# SHASwitch4.net
KiCad netlist of a schematic drawn in EAGLE
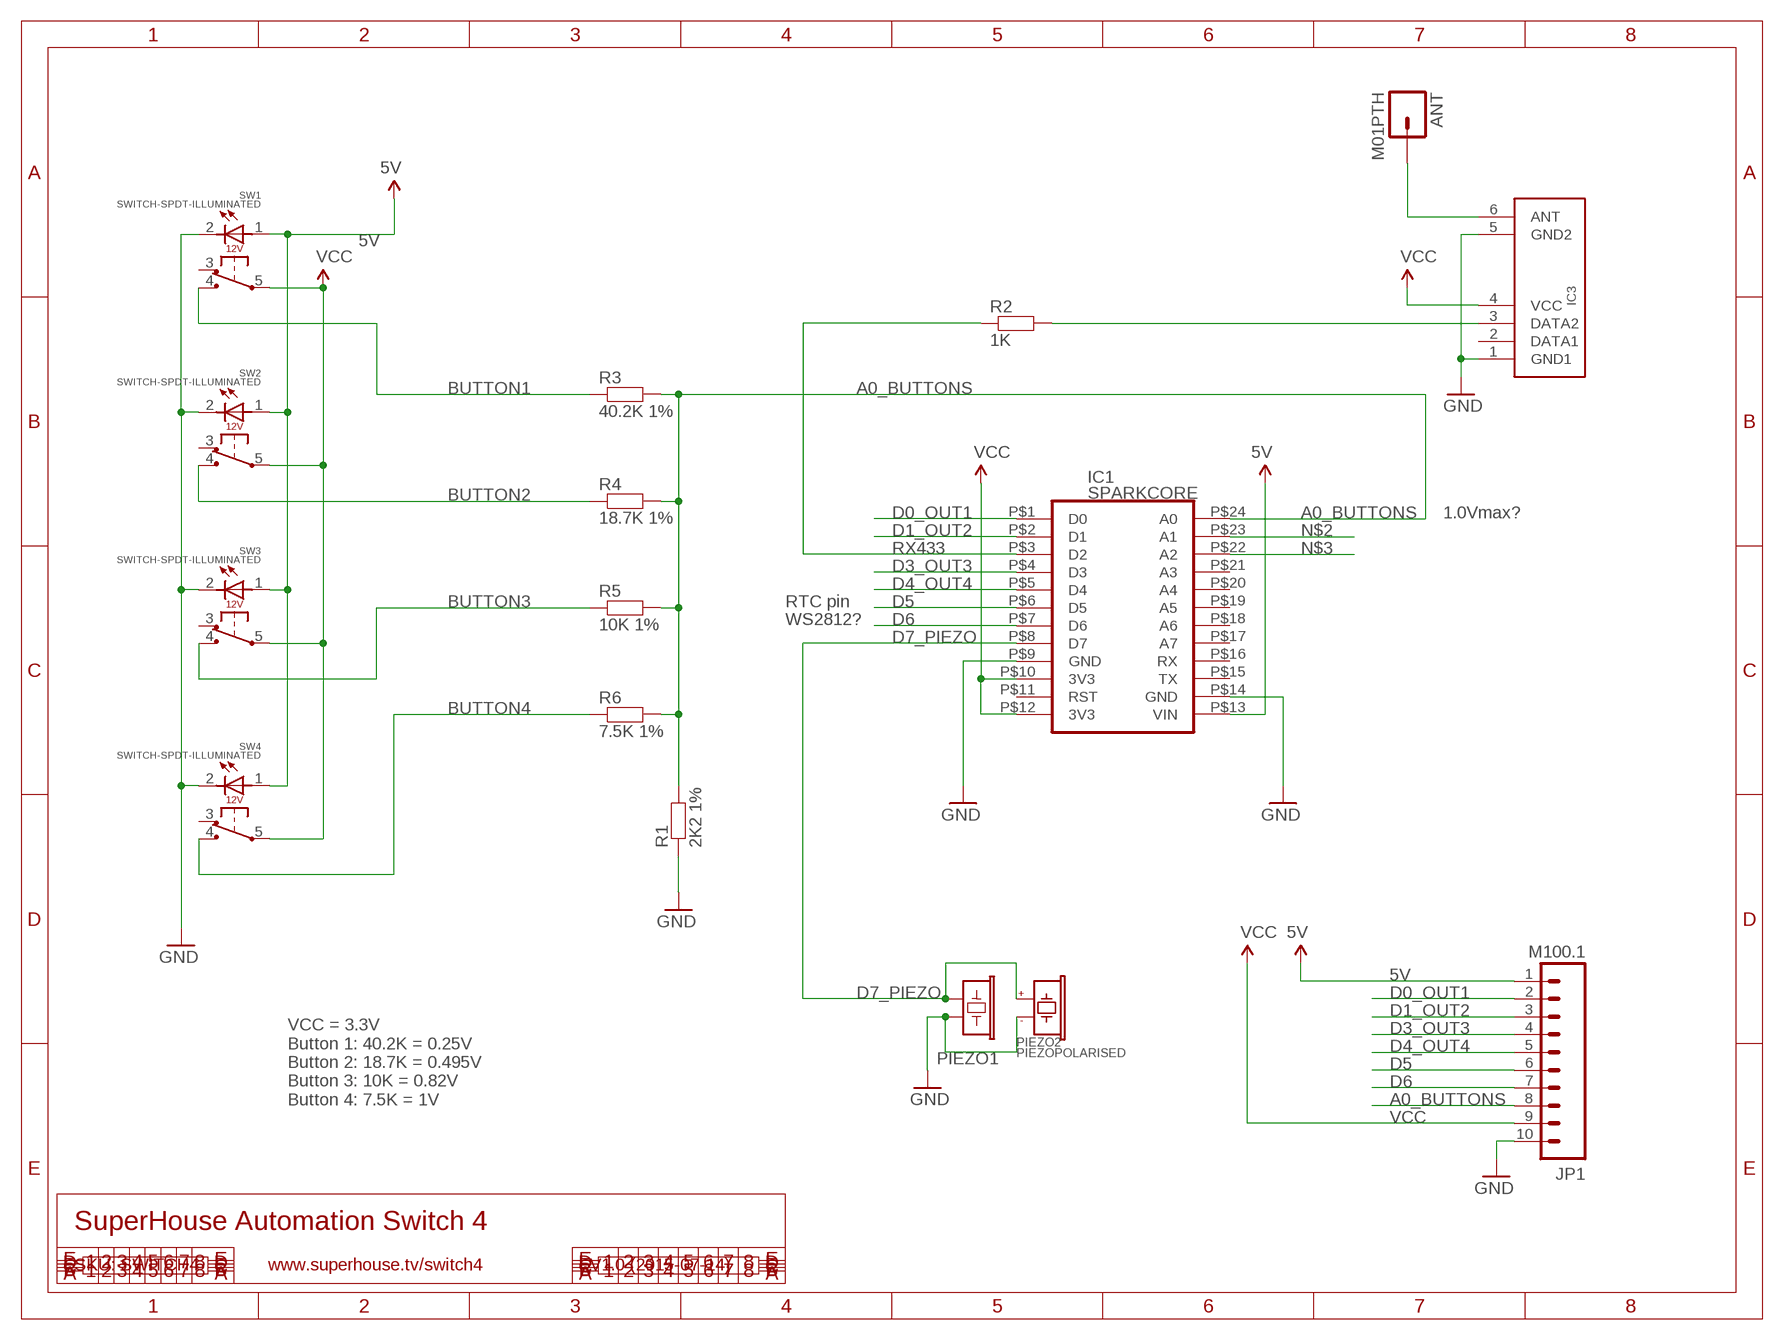
[diagram p0: schematic, sheet 1]

(export (version "E")
  (design (tool "Eeschema 10.0.6"))
  (components
    (comp (ref "ANT")
      (value "M01PTH")
      (footprint "eagle-import:1X01")
      (libsource (lib "eagle-import") (part "M01PTH"))
    )
    (comp (ref "IC1")
      (value "SPARKCORE")
      (footprint "eagle-import:SPARKCORE")
      (libsource (lib "eagle-import") (part "SPARKCORE"))
    )
    (comp (ref "IC3")
      (value "RXB1")
      (footprint "eagle-import:RX-B1-SHORT-FLAT")
      (libsource (lib "eagle-import") (part "RXB1SHORTFLAT"))
    )
    (comp (ref "JP1")
      (value "M100.1")
      (footprint "eagle-import:1X10")
      (libsource (lib "eagle-import") (part "M100.1"))
    )
    (comp (ref "PIEZO1")
      (value "BUZZERSMD12X12")
      (footprint "eagle-import:BUZZER-12X12-SMT")
      (libsource (lib "eagle-import") (part "BUZZERSMD12X12"))
    )
    (comp (ref "PIEZO2")
      (value "PIEZOPOLARISED")
      (footprint "eagle-import:PIEZO12MMWIDEPOLARISED")
      (libsource (lib "eagle-import") (part "PIEZOPOLARISED"))
    )
    (comp (ref "R1")
      (value "2K2 1%")
      (footprint "eagle-import:0603")
      (libsource (lib "eagle-import") (part "RESISTOR0603"))
    )
    (comp (ref "R2")
      (value "1K")
      (footprint "eagle-import:0603")
      (libsource (lib "eagle-import") (part "RESISTOR0603"))
    )
    (comp (ref "R3")
      (value "40.2K 1%")
      (footprint "eagle-import:0603")
      (libsource (lib "eagle-import") (part "RESISTOR0603"))
    )
    (comp (ref "R4")
      (value "18.7K 1%")
      (footprint "eagle-import:0603")
      (libsource (lib "eagle-import") (part "RESISTOR0603"))
    )
    (comp (ref "R5")
      (value "10K 1%")
      (footprint "eagle-import:0603")
      (libsource (lib "eagle-import") (part "RESISTOR0603"))
    )
    (comp (ref "R6")
      (value "7.5K 1%")
      (footprint "eagle-import:0603")
      (libsource (lib "eagle-import") (part "RESISTOR0603"))
    )
    (comp (ref "SW1")
      (value "SWITCH-SPDT-ILLUMINATED")
      (footprint "eagle-import:SWITCH-SPDT-ILLUMINATED")
      (libsource (lib "eagle-import") (part "SWITCH-SPDT-ILLUMINATED"))
    )
    (comp (ref "SW2")
      (value "SWITCH-SPDT-ILLUMINATED")
      (footprint "eagle-import:SWITCH-SPDT-ILLUMINATED")
      (libsource (lib "eagle-import") (part "SWITCH-SPDT-ILLUMINATED"))
    )
    (comp (ref "SW3")
      (value "SWITCH-SPDT-ILLUMINATED")
      (footprint "eagle-import:SWITCH-SPDT-ILLUMINATED")
      (libsource (lib "eagle-import") (part "SWITCH-SPDT-ILLUMINATED"))
    )
    (comp (ref "SW4")
      (value "SWITCH-SPDT-ILLUMINATED")
      (footprint "eagle-import:SWITCH-SPDT-ILLUMINATED")
      (libsource (lib "eagle-import") (part "SWITCH-SPDT-ILLUMINATED"))
    )
  )
  (nets
    (net (code "1") (name "/A0_BUTTONS") (class "Default")
      (node (ref "IC1") (pin "P$24") (pinfunction "A0_P$24") (pintype "bidirectional"))
      (node (ref "JP1") (pin "8") (pinfunction "8_8") (pintype "passive"))
      (node (ref "R1") (pin "2") (pinfunction "2_2") (pintype "passive"))
      (node (ref "R3") (pin "2") (pinfunction "2_2") (pintype "passive"))
      (node (ref "R4") (pin "2") (pinfunction "2_2") (pintype "passive"))
      (node (ref "R5") (pin "2") (pinfunction "2_2") (pintype "passive"))
      (node (ref "R6") (pin "2") (pinfunction "2_2") (pintype "passive"))
    )
    (net (code "2") (name "/BUTTON1") (class "Default")
      (node (ref "R3") (pin "1") (pinfunction "1_1") (pintype "passive"))
      (node (ref "SW1") (pin "4") (pinfunction "NO_4") (pintype "passive"))
    )
    (net (code "3") (name "/BUTTON2") (class "Default")
      (node (ref "R4") (pin "1") (pinfunction "1_1") (pintype "passive"))
      (node (ref "SW2") (pin "4") (pinfunction "NO_4") (pintype "passive"))
    )
    (net (code "4") (name "/BUTTON3") (class "Default")
      (node (ref "R5") (pin "1") (pinfunction "1_1") (pintype "passive"))
      (node (ref "SW3") (pin "4") (pinfunction "NO_4") (pintype "passive"))
    )
    (net (code "5") (name "/BUTTON4") (class "Default")
      (node (ref "R6") (pin "1") (pinfunction "1_1") (pintype "passive"))
      (node (ref "SW4") (pin "4") (pinfunction "NO_4") (pintype "passive"))
    )
    (net (code "6") (name "/D0_OUT1") (class "Default")
      (node (ref "IC1") (pin "P$1") (pinfunction "D0_P$1") (pintype "bidirectional"))
      (node (ref "JP1") (pin "2") (pinfunction "2_2") (pintype "passive"))
    )
    (net (code "7") (name "/D1_OUT2") (class "Default")
      (node (ref "IC1") (pin "P$2") (pinfunction "D1_P$2") (pintype "bidirectional"))
      (node (ref "JP1") (pin "3") (pinfunction "3_3") (pintype "passive"))
    )
    (net (code "8") (name "/D3_OUT3") (class "Default")
      (node (ref "IC1") (pin "P$4") (pinfunction "D3_P$4") (pintype "bidirectional"))
      (node (ref "JP1") (pin "4") (pinfunction "4_4") (pintype "passive"))
    )
    (net (code "9") (name "/D4_OUT4") (class "Default")
      (node (ref "IC1") (pin "P$5") (pinfunction "D4_P$5") (pintype "bidirectional"))
      (node (ref "JP1") (pin "5") (pinfunction "5_5") (pintype "passive"))
    )
    (net (code "10") (name "/D5") (class "Default")
      (node (ref "IC1") (pin "P$6") (pinfunction "D5_P$6") (pintype "bidirectional"))
      (node (ref "JP1") (pin "6") (pinfunction "6_6") (pintype "passive"))
    )
    (net (code "11") (name "/D6") (class "Default")
      (node (ref "IC1") (pin "P$7") (pinfunction "D6_P$7") (pintype "bidirectional"))
      (node (ref "JP1") (pin "7") (pinfunction "7_7") (pintype "passive"))
    )
    (net (code "12") (name "/D7_PIEZO") (class "Default")
      (node (ref "IC1") (pin "P$8") (pinfunction "D7_P$8") (pintype "bidirectional"))
      (node (ref "PIEZO1") (pin "1") (pinfunction "1_1") (pintype "passive"))
      (node (ref "PIEZO2") (pin "1") (pinfunction "+_1") (pintype "bidirectional"))
    )
    (net (code "13") (name "/N$2") (class "Default")
      (node (ref "IC1") (pin "P$23") (pinfunction "A1_P$23") (pintype "bidirectional"))
    )
    (net (code "14") (name "/N$3") (class "Default")
      (node (ref "IC1") (pin "P$22") (pinfunction "A2_P$22") (pintype "bidirectional"))
    )
    (net (code "15") (name "/RX433") (class "Default")
      (node (ref "IC1") (pin "P$3") (pinfunction "D2_P$3") (pintype "bidirectional"))
      (node (ref "R2") (pin "1") (pinfunction "1_1") (pintype "passive"))
    )
    (net (code "16") (name "5V") (class "Default")
      (node (ref "IC1") (pin "P$13") (pinfunction "VIN_P$13") (pintype "bidirectional"))
      (node (ref "JP1") (pin "1") (pinfunction "1_1") (pintype "passive"))
      (node (ref "SW1") (pin "1") (pinfunction "+_1") (pintype "passive"))
      (node (ref "SW2") (pin "1") (pinfunction "+_1") (pintype "passive"))
      (node (ref "SW3") (pin "1") (pinfunction "+_1") (pintype "passive"))
      (node (ref "SW4") (pin "1") (pinfunction "+_1") (pintype "passive"))
    )
    (net (code "17") (name "GND") (class "Default")
      (node (ref "IC1") (pin "P$14") (pinfunction "GND_P$14") (pintype "bidirectional"))
      (node (ref "IC1") (pin "P$9") (pinfunction "GND_P$9") (pintype "bidirectional"))
      (node (ref "IC3") (pin "1") (pinfunction "GND1_1") (pintype "bidirectional"))
      (node (ref "IC3") (pin "5") (pinfunction "GND2_5") (pintype "bidirectional"))
      (node (ref "JP1") (pin "10") (pinfunction "10_10") (pintype "passive"))
      (node (ref "PIEZO1") (pin "2") (pinfunction "2_2") (pintype "passive"))
      (node (ref "PIEZO2") (pin "2") (pinfunction "-_2") (pintype "bidirectional"))
      (node (ref "R1") (pin "1") (pinfunction "1_1") (pintype "passive"))
      (node (ref "SW1") (pin "2") (pinfunction "-_2") (pintype "passive"))
      (node (ref "SW2") (pin "2") (pinfunction "-_2") (pintype "passive"))
      (node (ref "SW3") (pin "2") (pinfunction "-_2") (pintype "passive"))
      (node (ref "SW4") (pin "2") (pinfunction "-_2") (pintype "passive"))
    )
    (net (code "18") (name "Net-(IC3-ANT)") (class "Default")
      (node (ref "ANT") (pin "1") (pinfunction "1_1") (pintype "passive"))
      (node (ref "IC3") (pin "6") (pinfunction "ANT_6") (pintype "bidirectional"))
    )
    (net (code "19") (name "Net-(IC3-DATA2)") (class "Default")
      (node (ref "IC3") (pin "3") (pinfunction "DATA2_3") (pintype "bidirectional"))
      (node (ref "R2") (pin "2") (pinfunction "2_2") (pintype "passive"))
    )
    (net (code "20") (name "VCC") (class "Default")
      (node (ref "IC1") (pin "P$10") (pinfunction "3V3_P$10") (pintype "bidirectional"))
      (node (ref "IC1") (pin "P$12") (pinfunction "3V3_P$12") (pintype "bidirectional"))
      (node (ref "IC3") (pin "4") (pinfunction "VCC_4") (pintype "bidirectional"))
      (node (ref "JP1") (pin "9") (pinfunction "9_9") (pintype "passive"))
      (node (ref "SW1") (pin "5") (pinfunction "COM_5") (pintype "passive"))
      (node (ref "SW2") (pin "5") (pinfunction "COM_5") (pintype "passive"))
      (node (ref "SW3") (pin "5") (pinfunction "COM_5") (pintype "passive"))
      (node (ref "SW4") (pin "5") (pinfunction "COM_5") (pintype "passive"))
    )
    (net (code "21") (name "unconnected-(IC1-A3-PadP$21)") (class "Default")
      (node (ref "IC1") (pin "P$21") (pinfunction "A3_P$21") (pintype "bidirectional"))
    )
    (net (code "22") (name "unconnected-(IC1-A4-PadP$20)") (class "Default")
      (node (ref "IC1") (pin "P$20") (pinfunction "A4_P$20") (pintype "bidirectional"))
    )
    (net (code "23") (name "unconnected-(IC1-A5-PadP$19)") (class "Default")
      (node (ref "IC1") (pin "P$19") (pinfunction "A5_P$19") (pintype "bidirectional"))
    )
    (net (code "24") (name "unconnected-(IC1-A6-PadP$18)") (class "Default")
      (node (ref "IC1") (pin "P$18") (pinfunction "A6_P$18") (pintype "bidirectional"))
    )
    (net (code "25") (name "unconnected-(IC1-A7-PadP$17)") (class "Default")
      (node (ref "IC1") (pin "P$17") (pinfunction "A7_P$17") (pintype "bidirectional"))
    )
    (net (code "26") (name "unconnected-(IC1-RST-PadP$11)") (class "Default")
      (node (ref "IC1") (pin "P$11") (pinfunction "RST_P$11") (pintype "bidirectional"))
    )
    (net (code "27") (name "unconnected-(IC1-RX-PadP$16)") (class "Default")
      (node (ref "IC1") (pin "P$16") (pinfunction "RX_P$16") (pintype "bidirectional"))
    )
    (net (code "28") (name "unconnected-(IC1-TX-PadP$15)") (class "Default")
      (node (ref "IC1") (pin "P$15") (pinfunction "TX_P$15") (pintype "bidirectional"))
    )
    (net (code "29") (name "unconnected-(IC3-DATA1-Pad2)") (class "Default")
      (node (ref "IC3") (pin "2") (pinfunction "DATA1_2") (pintype "bidirectional"))
    )
    (net (code "30") (name "unconnected-(SW1-NC-Pad3)") (class "Default")
      (node (ref "SW1") (pin "3") (pinfunction "NC_3") (pintype "passive"))
    )
    (net (code "31") (name "unconnected-(SW2-NC-Pad3)") (class "Default")
      (node (ref "SW2") (pin "3") (pinfunction "NC_3") (pintype "passive"))
    )
    (net (code "32") (name "unconnected-(SW3-NC-Pad3)") (class "Default")
      (node (ref "SW3") (pin "3") (pinfunction "NC_3") (pintype "passive"))
    )
    (net (code "33") (name "unconnected-(SW4-NC-Pad3)") (class "Default")
      (node (ref "SW4") (pin "3") (pinfunction "NC_3") (pintype "passive"))
    )
  )
)
